# tempLogger_Arduino.net
KiCad netlist of a schematic drawn in EAGLE
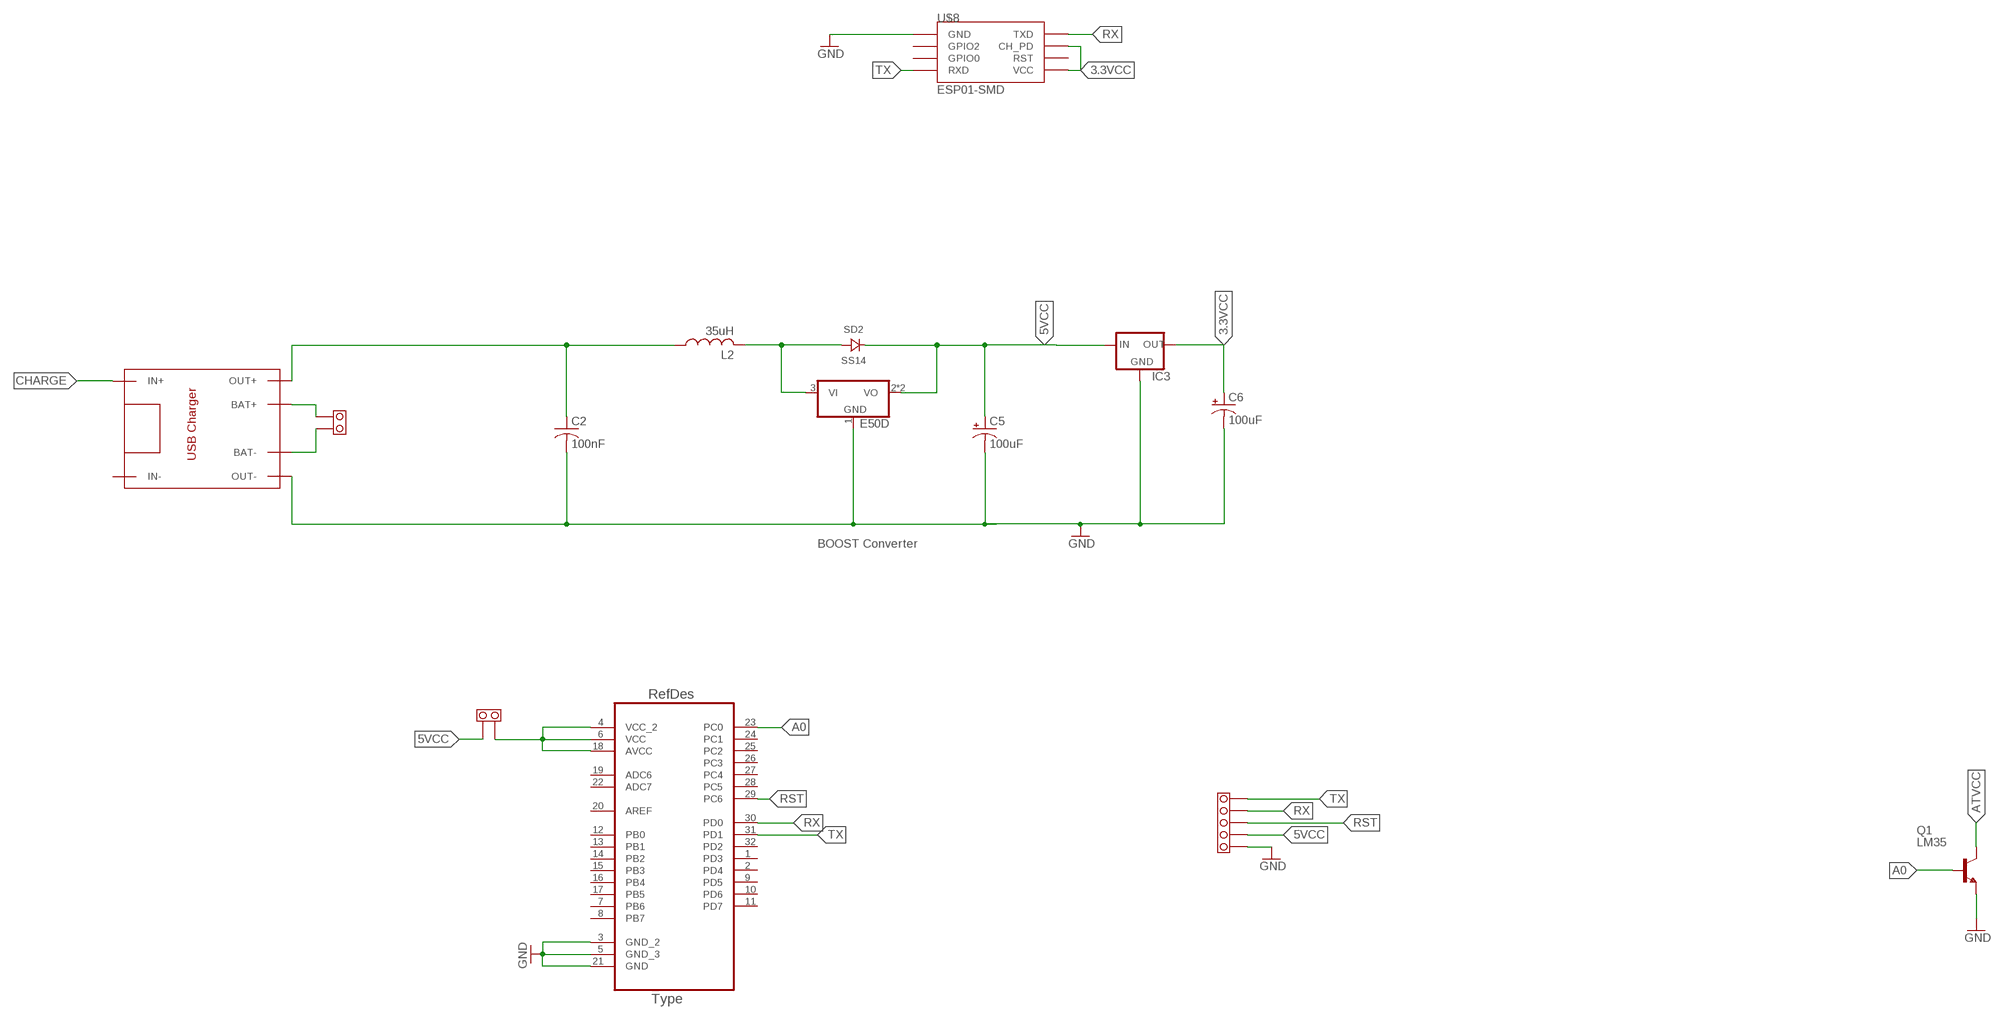
[diagram p0: schematic, sheet 1]

(export (version "E")
  (design (tool "Eeschema 10.0.6"))
  (components
    (comp (ref "C2")
      (value "100nF")
      (footprint "eagle-import:C1206")
      (libsource (lib "eagle-import") (part "C-USC1206"))
    )
    (comp (ref "C5")
      (value "100uF")
      (footprint "eagle-import:150CLZ-0810")
      (libsource (lib "eagle-import") (part "CPOL-US150CLZ-0810"))
    )
    (comp (ref "C6")
      (value "100uF")
      (footprint "eagle-import:153CLV-0405")
      (libsource (lib "eagle-import") (part "CPOL-US153CLV-0405"))
    )
    (comp (ref "IC2")
      (value "E50D")
      (footprint "eagle-import:SOT89")
      (libsource (lib "eagle-import") (part "E50D"))
    )
    (comp (ref "IC3")
      (value "LM1117")
      (footprint "eagle-import:SOT223")
      (libsource (lib "eagle-import") (part "LM1117"))
    )
    (comp (ref "L2")
      (value "35uH")
      (footprint "eagle-import:POWER-CHOKE_WE-TPC")
      (libsource (lib "eagle-import") (part "L-USWE-TPC"))
    )
    (comp (ref "Q1")
      (value "LM35")
      (footprint "eagle-import:TO92-EBC")
      (libsource (lib "eagle-import") (part "BC548"))
    )
    (comp (ref "SD2")
      (value "SS14")
      (footprint "eagle-import:DO214")
      (libsource (lib "eagle-import") (part "SS14"))
    )
    (comp (ref "U$2")
      (value "TP4056")
      (footprint "eagle-import:TP4056")
      (libsource (lib "eagle-import") (part "TP4056"))
    )
    (comp (ref "U$3")
      (value "BERG_5")
      (footprint "eagle-import:BERG_5")
      (libsource (lib "eagle-import") (part "BERG_5"))
    )
    (comp (ref "U$4")
      (value "BERG_2")
      (footprint "eagle-import:BERG_2")
      (libsource (lib "eagle-import") (part "BERG_2"))
    )
    (comp (ref "U$5")
      (value "BERG_2")
      (footprint "eagle-import:BERG_2")
      (libsource (lib "eagle-import") (part "BERG_2"))
    )
    (comp (ref "U$8")
      (value "ESP01-SMD")
      (footprint "eagle-import:ESP01_SMD")
      (libsource (lib "eagle-import") (part "ESP01-SMD"))
    )
    (comp (ref "U1")
      (value "ATMEGA328P-AU")
      (footprint "eagle-import:QFP80P900X900X120-32N")
      (libsource (lib "eagle-import") (part "ATMEGA328P-AU"))
    )
  )
  (nets
    (net (code "1") (name "3.3VCC") (class "Default")
      (node (ref "C6") (pin "+") (pinfunction "+_+") (pintype "passive"))
      (node (ref "IC3") (pin "2") (pinfunction "OUT_2") (pintype "passive"))
      (node (ref "U$8") (pin "CH_PD") (pinfunction "CH_PD_CH_PD") (pintype "bidirectional"))
      (node (ref "U$8") (pin "VCC") (pinfunction "VCC_VCC") (pintype "bidirectional"))
    )
    (net (code "2") (name "5VCC") (class "Default")
      (node (ref "C5") (pin "+") (pinfunction "+_+") (pintype "passive"))
      (node (ref "IC2") (pin "2") (pinfunction "VO_2") (pintype "passive"))
      (node (ref "IC2") (pin "2@1") (pinfunction "VO_2@1") (pintype "passive"))
      (node (ref "IC3") (pin "3") (pinfunction "IN_3") (pintype "input"))
      (node (ref "SD2") (pin "CATHODE") (pinfunction "CATHODE_CATHODE") (pintype "bidirectional"))
      (node (ref "U$3") (pin "H") (pinfunction "P$4_H") (pintype "bidirectional"))
      (node (ref "U$5") (pin "F") (pinfunction "P$2_F") (pintype "bidirectional"))
    )
    (net (code "3") (name "A0") (class "Default")
      (node (ref "Q1") (pin "B") (pinfunction "B_B") (pintype "passive"))
      (node (ref "U1") (pin "23") (pinfunction "PC0_23") (pintype "bidirectional"))
    )
    (net (code "4") (name "ATVCC") (class "Default")
      (node (ref "Q1") (pin "C") (pinfunction "C_C") (pintype "passive"))
      (node (ref "U$5") (pin "E") (pinfunction "P$1_E") (pintype "bidirectional"))
      (node (ref "U1") (pin "18") (pinfunction "AVCC_18") (pintype "power_in"))
      (node (ref "U1") (pin "4") (pinfunction "VCC_2_4") (pintype "power_in"))
      (node (ref "U1") (pin "6") (pinfunction "VCC_6") (pintype "power_in"))
    )
    (net (code "5") (name "CHARGE") (class "Default")
      (node (ref "U$2") (pin "IN+") (pinfunction "IN+_IN+") (pintype "bidirectional"))
    )
    (net (code "6") (name "GND") (class "Default")
      (node (ref "C2") (pin "2") (pinfunction "2_2") (pintype "passive"))
      (node (ref "C5") (pin "-") (pinfunction "-_-") (pintype "passive"))
      (node (ref "C6") (pin "-") (pinfunction "-_-") (pintype "passive"))
      (node (ref "IC2") (pin "1") (pinfunction "GND_1") (pintype "passive"))
      (node (ref "IC3") (pin "1") (pinfunction "GND_1") (pintype "input"))
      (node (ref "Q1") (pin "E") (pinfunction "E_E") (pintype "passive"))
      (node (ref "U$2") (pin "OUT-") (pinfunction "OUT-_OUT-") (pintype "bidirectional"))
      (node (ref "U$3") (pin "I") (pinfunction "P$5_I") (pintype "bidirectional"))
      (node (ref "U$8") (pin "GND") (pinfunction "GND_GND") (pintype "bidirectional"))
      (node (ref "U1") (pin "21") (pinfunction "GND_21") (pintype "passive"))
      (node (ref "U1") (pin "3") (pinfunction "GND_2_3") (pintype "passive"))
      (node (ref "U1") (pin "5") (pinfunction "GND_3_5") (pintype "passive"))
    )
    (net (code "7") (name "Net-(C2-Pad1)") (class "Default")
      (node (ref "C2") (pin "1") (pinfunction "1_1") (pintype "passive"))
      (node (ref "L2") (pin "1") (pinfunction "1_1") (pintype "passive"))
      (node (ref "U$2") (pin "OUT+") (pinfunction "OUT+_OUT+") (pintype "bidirectional"))
    )
    (net (code "8") (name "Net-(IC2-VI)") (class "Default")
      (node (ref "IC2") (pin "3") (pinfunction "VI_3") (pintype "input"))
      (node (ref "L2") (pin "2") (pinfunction "2_2") (pintype "passive"))
      (node (ref "SD2") (pin "ANODE") (pinfunction "ANODE_ANODE") (pintype "bidirectional"))
    )
    (net (code "9") (name "Net-(U$4-P$1)") (class "Default")
      (node (ref "U$2") (pin "BAT-") (pinfunction "BAT-_BAT-") (pintype "bidirectional"))
      (node (ref "U$4") (pin "E") (pinfunction "P$1_E") (pintype "bidirectional"))
    )
    (net (code "10") (name "Net-(U$4-P$2)") (class "Default")
      (node (ref "U$2") (pin "BAT+") (pinfunction "BAT+_BAT+") (pintype "bidirectional"))
      (node (ref "U$4") (pin "F") (pinfunction "P$2_F") (pintype "bidirectional"))
    )
    (net (code "11") (name "RST") (class "Default")
      (node (ref "U$3") (pin "G") (pinfunction "P$3_G") (pintype "bidirectional"))
      (node (ref "U1") (pin "29") (pinfunction "PC6_29") (pintype "bidirectional"))
    )
    (net (code "12") (name "RX") (class "Default")
      (node (ref "U$3") (pin "F") (pinfunction "P$2_F") (pintype "bidirectional"))
      (node (ref "U$8") (pin "TX") (pinfunction "TXD_TX") (pintype "bidirectional"))
      (node (ref "U1") (pin "30") (pinfunction "PD0_30") (pintype "bidirectional"))
    )
    (net (code "13") (name "TX") (class "Default")
      (node (ref "U$3") (pin "E") (pinfunction "P$1_E") (pintype "bidirectional"))
      (node (ref "U$8") (pin "RX") (pinfunction "RXD_RX") (pintype "bidirectional"))
      (node (ref "U1") (pin "31") (pinfunction "PD1_31") (pintype "bidirectional"))
    )
    (net (code "14") (name "unconnected-(U$2-PadIN-)") (class "Default")
      (node (ref "U$2") (pin "IN-") (pinfunction "IN-_IN-") (pintype "bidirectional"))
    )
    (net (code "15") (name "unconnected-(U$8-PadGPIO0)") (class "Default")
      (node (ref "U$8") (pin "GPIO0") (pinfunction "GPIO0_GPIO0") (pintype "bidirectional"))
    )
    (net (code "16") (name "unconnected-(U$8-PadGPIO2)") (class "Default")
      (node (ref "U$8") (pin "GPIO2") (pinfunction "GPIO2_GPIO2") (pintype "bidirectional"))
    )
    (net (code "17") (name "unconnected-(U$8-PadRST)") (class "Default")
      (node (ref "U$8") (pin "RST") (pinfunction "RST_RST") (pintype "bidirectional"))
    )
    (net (code "18") (name "unconnected-(U1-ADC6-Pad19)") (class "Default")
      (node (ref "U1") (pin "19") (pinfunction "ADC6_19") (pintype "input"))
    )
    (net (code "19") (name "unconnected-(U1-ADC7-Pad22)") (class "Default")
      (node (ref "U1") (pin "22") (pinfunction "ADC7_22") (pintype "input"))
    )
    (net (code "20") (name "unconnected-(U1-AREF-Pad20)") (class "Default")
      (node (ref "U1") (pin "20") (pinfunction "AREF_20") (pintype "input"))
    )
    (net (code "21") (name "unconnected-(U1-PB0-Pad12)") (class "Default")
      (node (ref "U1") (pin "12") (pinfunction "PB0_12") (pintype "bidirectional"))
    )
    (net (code "22") (name "unconnected-(U1-PB1-Pad13)") (class "Default")
      (node (ref "U1") (pin "13") (pinfunction "PB1_13") (pintype "bidirectional"))
    )
    (net (code "23") (name "unconnected-(U1-PB2-Pad14)") (class "Default")
      (node (ref "U1") (pin "14") (pinfunction "PB2_14") (pintype "bidirectional"))
    )
    (net (code "24") (name "unconnected-(U1-PB3-Pad15)") (class "Default")
      (node (ref "U1") (pin "15") (pinfunction "PB3_15") (pintype "bidirectional"))
    )
    (net (code "25") (name "unconnected-(U1-PB4-Pad16)") (class "Default")
      (node (ref "U1") (pin "16") (pinfunction "PB4_16") (pintype "bidirectional"))
    )
    (net (code "26") (name "unconnected-(U1-PB5-Pad17)") (class "Default")
      (node (ref "U1") (pin "17") (pinfunction "PB5_17") (pintype "bidirectional"))
    )
    (net (code "27") (name "unconnected-(U1-PB6-Pad7)") (class "Default")
      (node (ref "U1") (pin "7") (pinfunction "PB6_7") (pintype "bidirectional"))
    )
    (net (code "28") (name "unconnected-(U1-PB7-Pad8)") (class "Default")
      (node (ref "U1") (pin "8") (pinfunction "PB7_8") (pintype "bidirectional"))
    )
    (net (code "29") (name "unconnected-(U1-PC1-Pad24)") (class "Default")
      (node (ref "U1") (pin "24") (pinfunction "PC1_24") (pintype "bidirectional"))
    )
    (net (code "30") (name "unconnected-(U1-PC2-Pad25)") (class "Default")
      (node (ref "U1") (pin "25") (pinfunction "PC2_25") (pintype "bidirectional"))
    )
    (net (code "31") (name "unconnected-(U1-PC3-Pad26)") (class "Default")
      (node (ref "U1") (pin "26") (pinfunction "PC3_26") (pintype "bidirectional"))
    )
    (net (code "32") (name "unconnected-(U1-PC4-Pad27)") (class "Default")
      (node (ref "U1") (pin "27") (pinfunction "PC4_27") (pintype "bidirectional"))
    )
    (net (code "33") (name "unconnected-(U1-PC5-Pad28)") (class "Default")
      (node (ref "U1") (pin "28") (pinfunction "PC5_28") (pintype "bidirectional"))
    )
    (net (code "34") (name "unconnected-(U1-PD2-Pad32)") (class "Default")
      (node (ref "U1") (pin "32") (pinfunction "PD2_32") (pintype "bidirectional"))
    )
    (net (code "35") (name "unconnected-(U1-PD3-Pad1)") (class "Default")
      (node (ref "U1") (pin "1") (pinfunction "PD3_1") (pintype "bidirectional"))
    )
    (net (code "36") (name "unconnected-(U1-PD4-Pad2)") (class "Default")
      (node (ref "U1") (pin "2") (pinfunction "PD4_2") (pintype "bidirectional"))
    )
    (net (code "37") (name "unconnected-(U1-PD5-Pad9)") (class "Default")
      (node (ref "U1") (pin "9") (pinfunction "PD5_9") (pintype "bidirectional"))
    )
    (net (code "38") (name "unconnected-(U1-PD6-Pad10)") (class "Default")
      (node (ref "U1") (pin "10") (pinfunction "PD6_10") (pintype "bidirectional"))
    )
    (net (code "39") (name "unconnected-(U1-PD7-Pad11)") (class "Default")
      (node (ref "U1") (pin "11") (pinfunction "PD7_11") (pintype "bidirectional"))
    )
  )
)
